# Schematic_Borne_de_Recharge_VE.net
KiCad netlist of a schematic drawn in Altium Designer
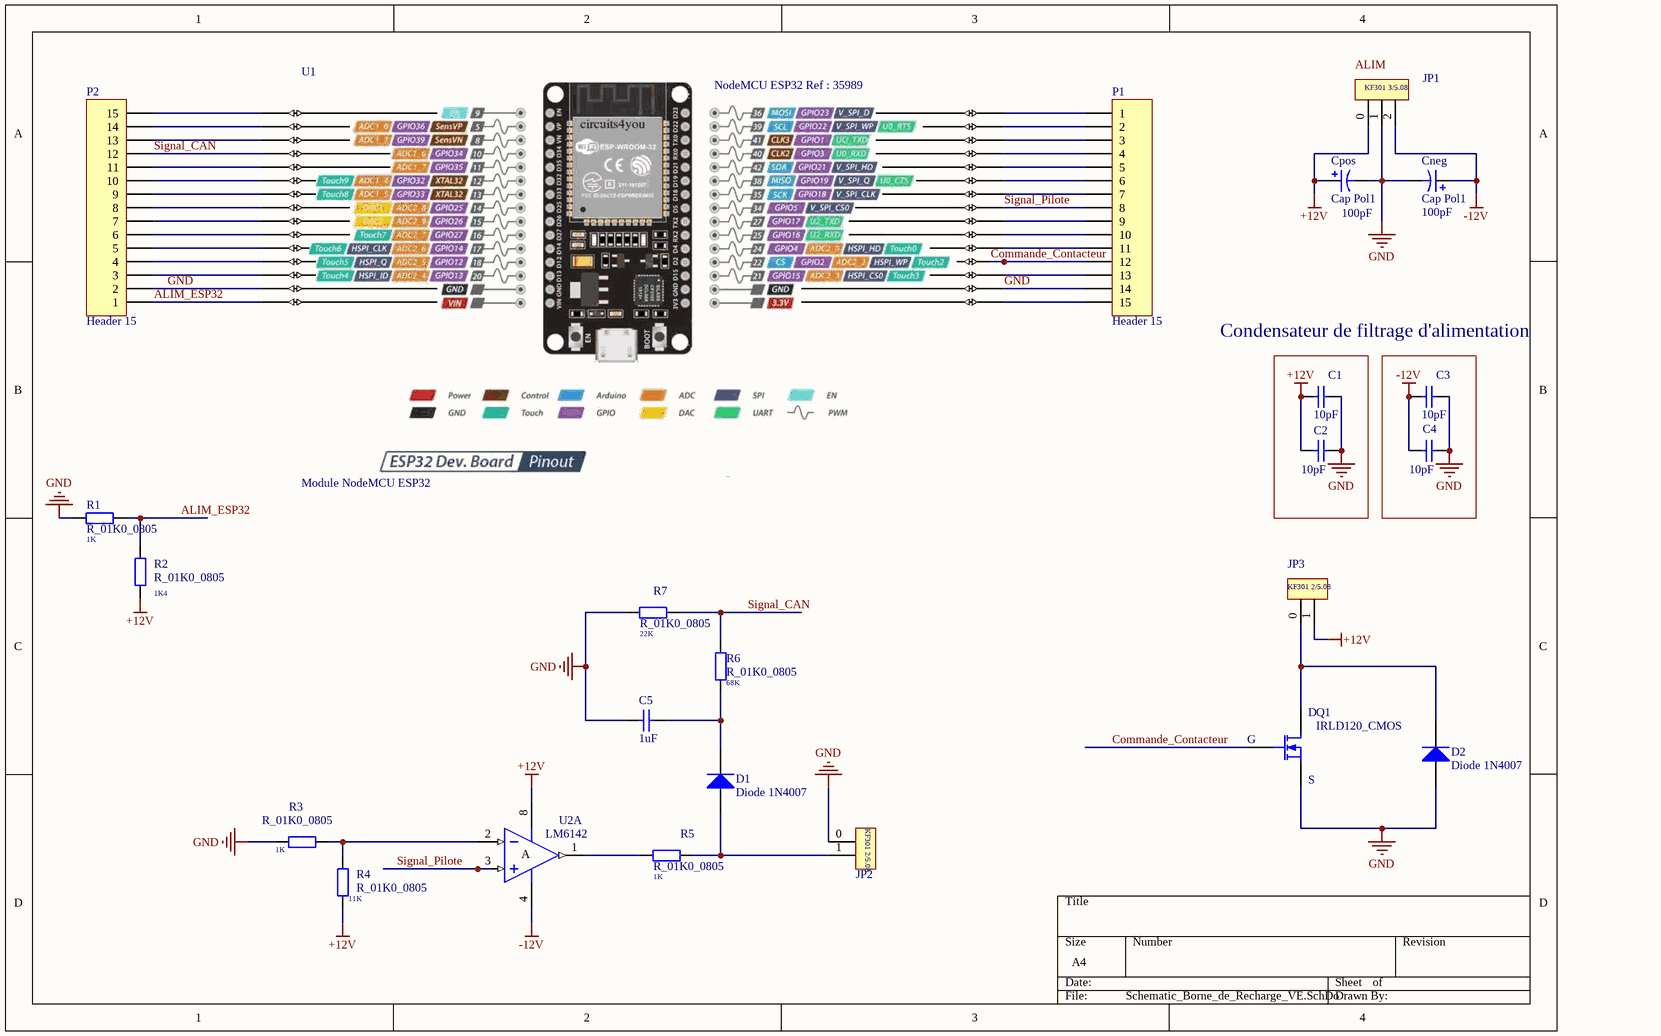
[diagram p0: Schematic_Borne_de_Recharge_VE.SchDoc]

(export (version "E")
  (design (tool "Eeschema 10.0.6"))
  (components
    (comp (ref "C1")
      (value "10pF")
      (footprint "AXIAL-0.3")
      (description "Capacitor")
      (fields (field (name "Comment") "Capacitor tantal") (field (name "PUBLISHER") "Altium Limited"))
      (libsource (lib "Library_Polytech_Passif") (part "Capacitor tantal"))
    )
    (comp (ref "C2")
      (value "10pF")
      (footprint "AXIAL-0.3")
      (description "Capacitor")
      (fields (field (name "Comment") "Capacitor tantal") (field (name "PUBLISHER") "Altium Limited"))
      (libsource (lib "Library_Polytech_Passif") (part "Capacitor tantal"))
    )
    (comp (ref "C3")
      (value "10pF")
      (footprint "AXIAL-0.3")
      (description "Capacitor")
      (fields (field (name "Comment") "Capacitor tantal") (field (name "PUBLISHER") "Altium Limited"))
      (libsource (lib "Library_Polytech_Passif") (part "Capacitor tantal"))
    )
    (comp (ref "C4")
      (value "10pF")
      (footprint "AXIAL-0.3")
      (description "Capacitor")
      (fields (field (name "Comment") "Capacitor tantal") (field (name "PUBLISHER") "Altium Limited"))
      (libsource (lib "Library_Polytech_Passif") (part "Capacitor tantal"))
    )
    (comp (ref "C5")
      (value "1uF")
      (footprint "AXIAL-0.3")
      (description "Capacitor")
      (fields (field (name "Comment") "Capacitor tantal") (field (name "PUBLISHER") "Altium Limited"))
      (libsource (lib "Library_Polytech_Passif") (part "Capacitor tantal"))
    )
    (comp (ref "Cneg")
      (value "Cap Pol1")
      (footprint "RB7.6-15")
      (description "Polarized Capacitor (Radial)")
      (fields (field (name "ALTIUM_VALUE") "100pF") (field (name "PUBLISHER") "Altium Limited"))
      (libsource (lib "Miscellaneous Devices") (part "Cap Pol1"))
    )
    (comp (ref "Cpos")
      (value "Cap Pol1")
      (footprint "RB7.6-15")
      (description "Polarized Capacitor (Radial)")
      (fields (field (name "ALTIUM_VALUE") "100pF") (field (name "PUBLISHER") "Altium Limited"))
      (libsource (lib "Miscellaneous Devices") (part "Cap Pol1"))
    )
    (comp (ref "D1")
      (value "Diode 1N4007")
      (footprint "DO-41")
      (description "1 Amp General Purpose Rectifier")
      (fields (field (name "PUBLISHER") "Altium Limited"))
      (libsource (lib "Miscellaneous Devices") (part "Diode 1N4007"))
    )
    (comp (ref "D2")
      (value "Diode 1N4007")
      (footprint "DO-41")
      (description "1 Amp General Purpose Rectifier")
      (fields (field (name "PUBLISHER") "Altium Limited"))
      (libsource (lib "Miscellaneous Devices") (part "Diode 1N4007"))
    )
    (comp (ref "JP1")
      (value "Screw Terminal 3/5.08")
      (footprint "KF301_3/5.08")
      (description "KF301 3 contacts / 5.08 mm")
      (libsource (lib "Library_Polytech_Connector") (part "Screw Terminal 3/5.08"))
    )
    (comp (ref "JP2")
      (value "Screw Terminal 2/5.08")
      (footprint "KF301_2/5.08")
      (description "KF301 2 contacts / 5.08mm")
      (libsource (lib "") (part "Screw Terminal 2/5.08_1"))
    )
    (comp (ref "JP3")
      (value "Screw Terminal 2/5.08")
      (footprint "KF301_2/5.08")
      (description "KF301 2 contacts / 5.08mm")
      (libsource (lib "Library_Polytech_Connector") (part "Screw Terminal 2/5.08"))
    )
    (comp (ref "P1")
      (value "Header 15")
      (footprint "HDR1X15")
      (description "Header, 15-Pin")
      (fields (field (name "PUBLISHER") "Altium Limited"))
      (libsource (lib "Miscellaneous Connectors") (part "Header 15"))
    )
    (comp (ref "P2")
      (value "Header 15")
      (footprint "HDR1X15")
      (description "Header, 15-Pin")
      (fields (field (name "PUBLISHER") "Altium Limited"))
      (libsource (lib "") (part "Header 15_1"))
    )
    (comp (ref "Q1")
      (value "IRLD120_CMOS")
      (footprint "TO-250")
      (description "N-Channel MOSFET")
      (fields (field (name "PUBLISHER") "Altium Limited"))
      (libsource (lib "Library_Polytech_Actif") (part "IRLD120"))
    )
    (comp (ref "R1")
      (value "R_01K0_0805")
      (footprint "RESC2012X05N")
      (description "Resistor 1K Ohms 1/4W 0805 1%")
      (fields (field (name "ALTIUM_VALUE") "1K"))
      (libsource (lib "Polytech_CMS") (part "R_01K0_0805"))
    )
    (comp (ref "R2")
      (value "R_01K0_0805")
      (footprint "RESC2012X05N")
      (description "Resistor 1K Ohms 1/4W 0805 1%")
      (fields (field (name "ALTIUM_VALUE") "1K4"))
      (libsource (lib "") (part "R_01K0_0805_1"))
    )
    (comp (ref "R3")
      (value "R_01K0_0805")
      (footprint "RESC2012X05N")
      (description "Resistor 1K Ohms 1/4W 0805 1%")
      (fields (field (name "ALTIUM_VALUE") "1K"))
      (libsource (lib "") (part "R_01K0_0805_2"))
    )
    (comp (ref "R4")
      (value "R_01K0_0805")
      (footprint "RESC2012X05N")
      (description "Resistor 1K Ohms 1/4W 0805 1%")
      (fields (field (name "ALTIUM_VALUE") "11K"))
      (libsource (lib "") (part "R_01K0_0805_1"))
    )
    (comp (ref "R5")
      (value "R_01K0_0805")
      (footprint "RESC2012X05N")
      (description "Resistor 1K Ohms 1/4W 0805 1%")
      (fields (field (name "ALTIUM_VALUE") "1K"))
      (libsource (lib "") (part "R_01K0_0805_2"))
    )
    (comp (ref "R6")
      (value "R_01K0_0805")
      (footprint "RESC2012X05N")
      (description "Resistor 1K Ohms 1/4W 0805 1%")
      (fields (field (name "ALTIUM_VALUE") "68K"))
      (libsource (lib "") (part "R_01K0_0805_1"))
    )
    (comp (ref "R7")
      (value "R_01K0_0805")
      (footprint "RESC2012X05N")
      (description "Resistor 1K Ohms 1/4W 0805 1%")
      (fields (field (name "ALTIUM_VALUE") "22K"))
      (libsource (lib "") (part "R_01K0_0805_2"))
    )
    (comp (ref "U1")
      (value "Module NodeMCU ESP32")
      (footprint "NodeMCU ESP32")
      (libsource (lib "Library_Polytech_Actif") (part "NodeMCU ESP 32"))
    )
    (comp (ref "U2")
      (value "LM6142")
      (footprint "DIL 8")
      (description "17 MHz Rail-to-Rail Input-Output Operational Amplifier")
      (fields (field (name "PUBLISHER") "Altium Limited"))
      (libsource (lib "Library_Polytech_Actif (1)") (part "LM6142"))
    )
  )
  (nets
    (net (code "1") (name "+12V") (class "Default")
      (node (ref "C1") (pin "1") (pinfunction "1_1") (pintype "passive"))
      (node (ref "C2") (pin "1") (pinfunction "1_1") (pintype "passive"))
      (node (ref "Cpos") (pin "1") (pinfunction "1_1") (pintype "passive"))
      (node (ref "JP1") (pin "0") (pinfunction "0_0") (pintype "passive"))
      (node (ref "JP3") (pin "1") (pinfunction "1_1") (pintype "passive"))
      (node (ref "R2") (pin "1") (pinfunction "1_1") (pintype "passive"))
      (node (ref "R4") (pin "1") (pinfunction "1_1") (pintype "passive"))
      (node (ref "U2") (pin "8") (pinfunction "V+_8") (pintype "power_in"))
    )
    (net (code "2") (name "-12V") (class "Default")
      (node (ref "C3") (pin "1") (pinfunction "1_1") (pintype "passive"))
      (node (ref "C4") (pin "1") (pinfunction "1_1") (pintype "passive"))
      (node (ref "Cneg") (pin "1") (pinfunction "1_1") (pintype "passive"))
      (node (ref "JP1") (pin "2") (pinfunction "2_2") (pintype "passive"))
      (node (ref "U2") (pin "4") (pinfunction "V-_4") (pintype "power_in"))
    )
    (net (code "4") (name "/ALIM_ESP32") (class "Default")
      (node (ref "P2") (pin "1") (pinfunction "1_1") (pintype "passive"))
      (node (ref "R1") (pin "1") (pinfunction "1_1") (pintype "passive"))
      (node (ref "R2") (pin "2") (pinfunction "2_2") (pintype "passive"))
      (node (ref "U1") (pin "15") (pinfunction "Vin_15") (pintype "bidirectional"))
    )
    (net (code "5") (name "/Commande_Contacteur") (class "Default")
      (node (ref "P1") (pin "12") (pinfunction "12_12") (pintype "passive"))
      (node (ref "Q1") (pin "3") (pinfunction "G_3") (pintype "passive"))
      (node (ref "U1") (pin "19") (pinfunction "D2_19") (pintype "bidirectional"))
    )
    (net (code "6") (name "/Signal_CAN") (class "Default")
      (node (ref "P2") (pin "12") (pinfunction "12_12") (pintype "passive"))
      (node (ref "R6") (pin "2") (pinfunction "2_2") (pintype "passive"))
      (node (ref "R7") (pin "2") (pinfunction "2_2") (pintype "passive"))
      (node (ref "U1") (pin "4") (pinfunction "D34_4") (pintype "bidirectional"))
    )
    (net (code "7") (name "/Signal_Pilote") (class "Default")
      (node (ref "P1") (pin "8") (pinfunction "8_8") (pintype "passive"))
      (node (ref "U1") (pin "23") (pinfunction "D5_23") (pintype "bidirectional"))
      (node (ref "U2") (pin "3") (pinfunction "IN+_3") (pintype "input"))
    )
    (net (code "8") (name "GND") (class "Default")
      (node (ref "C1") (pin "2") (pinfunction "2_2") (pintype "passive"))
      (node (ref "C2") (pin "2") (pinfunction "2_2") (pintype "passive"))
      (node (ref "C3") (pin "2") (pinfunction "2_2") (pintype "passive"))
      (node (ref "C4") (pin "2") (pinfunction "2_2") (pintype "passive"))
      (node (ref "C5") (pin "2") (pinfunction "2_2") (pintype "passive"))
      (node (ref "Cneg") (pin "2") (pinfunction "2_2") (pintype "passive"))
      (node (ref "Cpos") (pin "2") (pinfunction "2_2") (pintype "passive"))
      (node (ref "D2") (pin "1") (pinfunction "A_1") (pintype "passive"))
      (node (ref "JP1") (pin "1") (pinfunction "1_1") (pintype "passive"))
      (node (ref "JP2") (pin "0") (pinfunction "0_0") (pintype "passive"))
      (node (ref "P1") (pin "14") (pinfunction "14_14") (pintype "passive"))
      (node (ref "P2") (pin "2") (pinfunction "2_2") (pintype "passive"))
      (node (ref "Q1") (pin "2") (pinfunction "S_2") (pintype "passive"))
      (node (ref "R1") (pin "2") (pinfunction "2_2") (pintype "passive"))
      (node (ref "R3") (pin "1") (pinfunction "1_1") (pintype "passive"))
      (node (ref "R7") (pin "1") (pinfunction "1_1") (pintype "passive"))
      (node (ref "U1") (pin "14") (pinfunction "GND_14") (pintype "bidirectional"))
      (node (ref "U1") (pin "17") (pinfunction "GND_17") (pintype "bidirectional"))
    )
    (net (code "9") (name "Net-(D1-A)") (class "Default")
      (node (ref "D1") (pin "1") (pinfunction "A_1") (pintype "passive"))
      (node (ref "JP2") (pin "1") (pinfunction "1_1") (pintype "passive"))
      (node (ref "R5") (pin "2") (pinfunction "2_2") (pintype "passive"))
    )
    (net (code "10") (name "Net-(D1-K)") (class "Default")
      (node (ref "C5") (pin "1") (pinfunction "1_1") (pintype "passive"))
      (node (ref "D1") (pin "2") (pinfunction "K_2") (pintype "passive"))
      (node (ref "R6") (pin "1") (pinfunction "1_1") (pintype "passive"))
    )
    (net (code "11") (name "Net-(D2-K)") (class "Default")
      (node (ref "D2") (pin "2") (pinfunction "K_2") (pintype "passive"))
      (node (ref "JP3") (pin "0") (pinfunction "0_0") (pintype "passive"))
      (node (ref "Q1") (pin "1") (pinfunction "D_1") (pintype "passive"))
    )
    (net (code "12") (name "Net-(U1-3V3)") (class "Default")
      (node (ref "P1") (pin "15") (pinfunction "15_15") (pintype "passive"))
      (node (ref "U1") (pin "16") (pinfunction "3V3_16") (pintype "bidirectional"))
    )
    (net (code "13") (name "Net-(U1-D4)") (class "Default")
      (node (ref "P1") (pin "11") (pinfunction "11_11") (pintype "passive"))
      (node (ref "U1") (pin "20") (pinfunction "D4_20") (pintype "bidirectional"))
    )
    (net (code "14") (name "Net-(U1-D12)") (class "Default")
      (node (ref "P2") (pin "4") (pinfunction "4_4") (pintype "passive"))
      (node (ref "U1") (pin "12") (pinfunction "D12_12") (pintype "bidirectional"))
    )
    (net (code "15") (name "Net-(U1-D13)") (class "Default")
      (node (ref "P2") (pin "3") (pinfunction "3_3") (pintype "passive"))
      (node (ref "U1") (pin "13") (pinfunction "D13_13") (pintype "bidirectional"))
    )
    (net (code "16") (name "Net-(U1-D14)") (class "Default")
      (node (ref "P2") (pin "5") (pinfunction "5_5") (pintype "passive"))
      (node (ref "U1") (pin "11") (pinfunction "D14_11") (pintype "bidirectional"))
    )
    (net (code "17") (name "Net-(U1-D15)") (class "Default")
      (node (ref "P1") (pin "13") (pinfunction "13_13") (pintype "passive"))
      (node (ref "U1") (pin "18") (pinfunction "D15_18") (pintype "bidirectional"))
    )
    (net (code "18") (name "Net-(U1-D18)") (class "Default")
      (node (ref "P1") (pin "7") (pinfunction "7_7") (pintype "passive"))
      (node (ref "U1") (pin "24") (pinfunction "D18_24") (pintype "bidirectional"))
    )
    (net (code "19") (name "Net-(U1-D19)") (class "Default")
      (node (ref "P1") (pin "6") (pinfunction "6_6") (pintype "passive"))
      (node (ref "U1") (pin "25") (pinfunction "D19_25") (pintype "bidirectional"))
    )
    (net (code "20") (name "Net-(U1-D21)") (class "Default")
      (node (ref "P1") (pin "5") (pinfunction "5_5") (pintype "passive"))
      (node (ref "U1") (pin "26") (pinfunction "D21_26") (pintype "bidirectional"))
    )
    (net (code "21") (name "Net-(U1-D22)") (class "Default")
      (node (ref "P1") (pin "2") (pinfunction "2_2") (pintype "passive"))
      (node (ref "U1") (pin "29") (pinfunction "D22_29") (pintype "bidirectional"))
    )
    (net (code "22") (name "Net-(U1-D23)") (class "Default")
      (node (ref "P1") (pin "1") (pinfunction "1_1") (pintype "passive"))
      (node (ref "U1") (pin "30") (pinfunction "D23_30") (pintype "bidirectional"))
    )
    (net (code "23") (name "Net-(U1-D25)") (class "Default")
      (node (ref "P2") (pin "8") (pinfunction "8_8") (pintype "passive"))
      (node (ref "U1") (pin "8") (pinfunction "D25_8") (pintype "bidirectional"))
    )
    (net (code "24") (name "Net-(U1-D26)") (class "Default")
      (node (ref "P2") (pin "7") (pinfunction "7_7") (pintype "passive"))
      (node (ref "U1") (pin "9") (pinfunction "D26_9") (pintype "bidirectional"))
    )
    (net (code "25") (name "Net-(U1-D27)") (class "Default")
      (node (ref "P2") (pin "6") (pinfunction "6_6") (pintype "passive"))
      (node (ref "U1") (pin "10") (pinfunction "D27_10") (pintype "bidirectional"))
    )
    (net (code "26") (name "Net-(U1-D32)") (class "Default")
      (node (ref "P2") (pin "10") (pinfunction "10_10") (pintype "passive"))
      (node (ref "U1") (pin "6") (pinfunction "D32_6") (pintype "bidirectional"))
    )
    (net (code "27") (name "Net-(U1-D33)") (class "Default")
      (node (ref "P2") (pin "9") (pinfunction "9_9") (pintype "passive"))
      (node (ref "U1") (pin "7") (pinfunction "D33_7") (pintype "bidirectional"))
    )
    (net (code "28") (name "Net-(U1-D35)") (class "Default")
      (node (ref "P2") (pin "11") (pinfunction "11_11") (pintype "passive"))
      (node (ref "U1") (pin "5") (pinfunction "D35_5") (pintype "bidirectional"))
    )
    (net (code "29") (name "Net-(U1-EN)") (class "Default")
      (node (ref "P2") (pin "15") (pinfunction "15_15") (pintype "passive"))
      (node (ref "U1") (pin "1") (pinfunction "EN_1") (pintype "bidirectional"))
    )
    (net (code "30") (name "Net-(U1-RX0)") (class "Default")
      (node (ref "P1") (pin "4") (pinfunction "4_4") (pintype "passive"))
      (node (ref "U1") (pin "27") (pinfunction "RX0_27") (pintype "bidirectional"))
    )
    (net (code "31") (name "Net-(U1-RX2)") (class "Default")
      (node (ref "P1") (pin "10") (pinfunction "10_10") (pintype "passive"))
      (node (ref "U1") (pin "21") (pinfunction "RX2_21") (pintype "bidirectional"))
    )
    (net (code "32") (name "Net-(U1-TX0)") (class "Default")
      (node (ref "P1") (pin "3") (pinfunction "3_3") (pintype "passive"))
      (node (ref "U1") (pin "28") (pinfunction "TX0_28") (pintype "bidirectional"))
    )
    (net (code "33") (name "Net-(U1-TX2)") (class "Default")
      (node (ref "P1") (pin "9") (pinfunction "9_9") (pintype "passive"))
      (node (ref "U1") (pin "22") (pinfunction "TX2_22") (pintype "bidirectional"))
    )
    (net (code "34") (name "Net-(U1-VN)") (class "Default")
      (node (ref "P2") (pin "13") (pinfunction "13_13") (pintype "passive"))
      (node (ref "U1") (pin "3") (pinfunction "VN_3") (pintype "bidirectional"))
    )
    (net (code "35") (name "Net-(U1-VP)") (class "Default")
      (node (ref "P2") (pin "14") (pinfunction "14_14") (pintype "passive"))
      (node (ref "U1") (pin "2") (pinfunction "VP_2") (pintype "bidirectional"))
    )
    (net (code "36") (name "Net-(U2A-IN-)") (class "Default")
      (node (ref "R3") (pin "2") (pinfunction "2_2") (pintype "passive"))
      (node (ref "R4") (pin "2") (pinfunction "2_2") (pintype "passive"))
      (node (ref "U2") (pin "2") (pinfunction "IN-_2") (pintype "input"))
    )
    (net (code "37") (name "Net-(U2A-OUT)") (class "Default")
      (node (ref "R5") (pin "1") (pinfunction "1_1") (pintype "passive"))
      (node (ref "U2") (pin "1") (pinfunction "OUT_1") (pintype "output"))
    )
  )
)
